# Dhuma.net
KiCad netlist of a schematic drawn in EAGLE
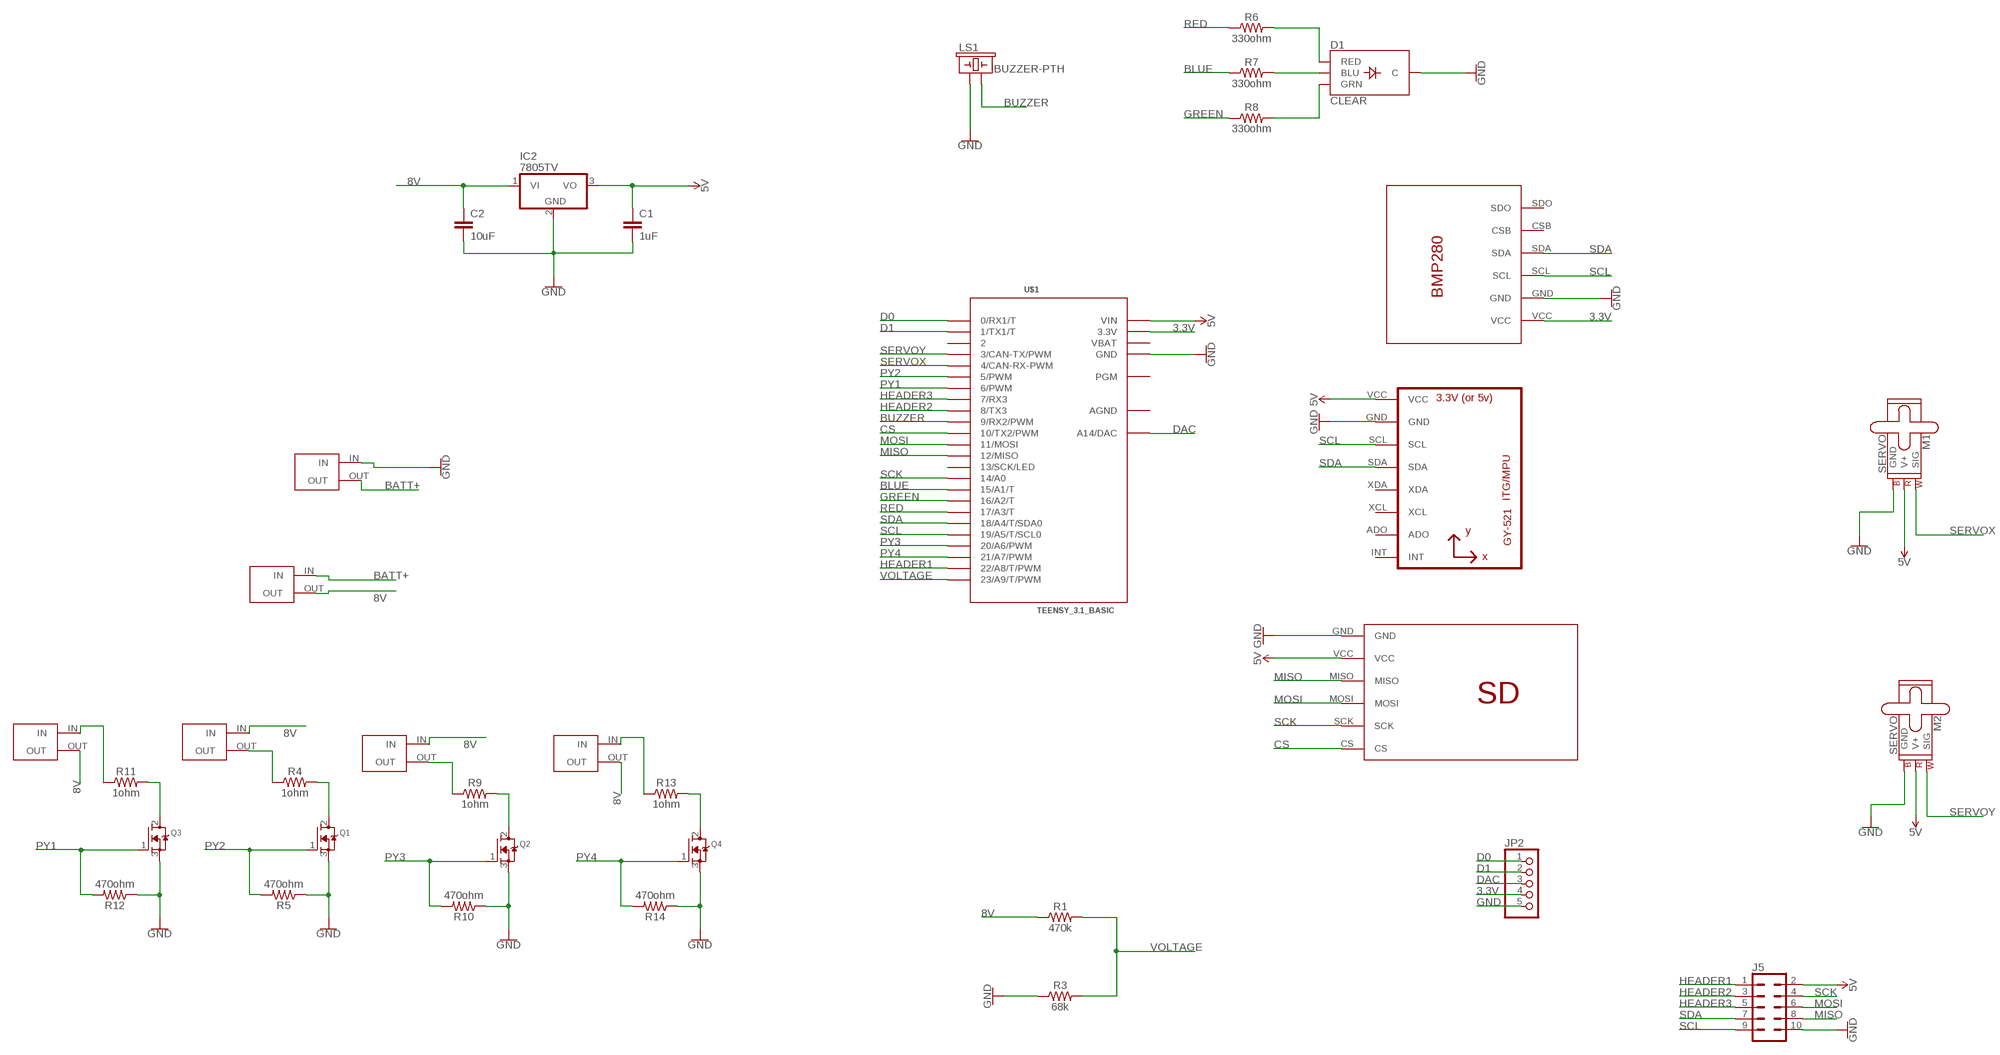
[diagram p0: schematic, sheet 1]

(export (version "E")
  (design (tool "Eeschema 10.0.6"))
  (components
    (comp (ref "C1")
      (value "1uF")
      (footprint "eagle-import:CAP-PTH-2.54")
      (libsource (lib "eagle-import") (part "22PF-PTH-2.54MM-200V-5%"))
    )
    (comp (ref "C2")
      (value "10uF")
      (footprint "eagle-import:CAP-PTH-2.54")
      (libsource (lib "eagle-import") (part "22PF-PTH-2.54MM-200V-5%"))
    )
    (comp (ref "D1")
      (value "CLEAR")
      (footprint "eagle-import:LED-RGB-THRU")
      (libsource (lib "eagle-import") (part "LED-RGB-CCCLEAR"))
    )
    (comp (ref "IC2")
      (value "7805TV")
      (footprint "eagle-import:TO220V")
      (libsource (lib "eagle-import") (part "78TV05"))
    )
    (comp (ref "J5")
      (value "CONN_05X2NO_SILK")
      (footprint "eagle-import:2X5_NOSILK")
      (libsource (lib "eagle-import") (part "CONN_05X2NO_SILK"))
    )
    (comp (ref "JP2")
      (value "PINHD-1X5")
      (footprint "eagle-import:1X05")
      (libsource (lib "eagle-import") (part "PINHD-1X5"))
    )
    (comp (ref "LS1")
      (value "BUZZER-PTH")
      (footprint "eagle-import:BUZZER-12MM")
      (libsource (lib "eagle-import") (part "BUZZER-PTH"))
    )
    (comp (ref "M1")
      (value "SERVO")
      (footprint "eagle-import:1X03")
      (libsource (lib "eagle-import") (part "SERVO"))
    )
    (comp (ref "M2")
      (value "SERVO")
      (footprint "eagle-import:1X03")
      (libsource (lib "eagle-import") (part "SERVO"))
    )
    (comp (ref "Q1")
      (value "MOSFET-NGDS_TO220V")
      (footprint "eagle-import:TO220V")
      (libsource (lib "eagle-import") (part "MOSFET-NGDS_TO220V"))
    )
    (comp (ref "Q2")
      (value "MOSFET-NGDS_TO220V")
      (footprint "eagle-import:TO220V")
      (libsource (lib "eagle-import") (part "MOSFET-NGDS_TO220V"))
    )
    (comp (ref "Q3")
      (value "MOSFET-NGDS_TO220V")
      (footprint "eagle-import:TO220V")
      (libsource (lib "eagle-import") (part "MOSFET-NGDS_TO220V"))
    )
    (comp (ref "Q4")
      (value "MOSFET-NGDS_TO220V")
      (footprint "eagle-import:TO220V")
      (libsource (lib "eagle-import") (part "MOSFET-NGDS_TO220V"))
    )
    (comp (ref "R1")
      (value "470k")
      (footprint "eagle-import:AXIAL-0.3")
      (libsource (lib "eagle-import") (part "10OHM-HORIZ-1/4W-1%"))
    )
    (comp (ref "R3")
      (value "68k")
      (footprint "eagle-import:AXIAL-0.3")
      (libsource (lib "eagle-import") (part "10OHM-HORIZ-1/4W-1%"))
    )
    (comp (ref "R4")
      (value "1ohm")
      (footprint "eagle-import:AXIAL-0.3")
      (libsource (lib "eagle-import") (part "10OHM-HORIZ-1/4W-1%"))
    )
    (comp (ref "R5")
      (value "470ohm")
      (footprint "eagle-import:AXIAL-0.3")
      (libsource (lib "eagle-import") (part "10OHM-HORIZ-1/4W-1%"))
    )
    (comp (ref "R6")
      (value "330ohm")
      (footprint "eagle-import:AXIAL-0.3")
      (libsource (lib "eagle-import") (part "10OHM-HORIZ-1/4W-1%"))
    )
    (comp (ref "R7")
      (value "330ohm")
      (footprint "eagle-import:AXIAL-0.3")
      (libsource (lib "eagle-import") (part "10OHM-HORIZ-1/4W-1%"))
    )
    (comp (ref "R8")
      (value "330ohm")
      (footprint "eagle-import:AXIAL-0.3")
      (libsource (lib "eagle-import") (part "10OHM-HORIZ-1/4W-1%"))
    )
    (comp (ref "R9")
      (value "1ohm")
      (footprint "eagle-import:AXIAL-0.3")
      (libsource (lib "eagle-import") (part "10OHM-HORIZ-1/4W-1%"))
    )
    (comp (ref "R10")
      (value "470ohm")
      (footprint "eagle-import:AXIAL-0.3")
      (libsource (lib "eagle-import") (part "10OHM-HORIZ-1/4W-1%"))
    )
    (comp (ref "R11")
      (value "1ohm")
      (footprint "eagle-import:AXIAL-0.3")
      (libsource (lib "eagle-import") (part "10OHM-HORIZ-1/4W-1%"))
    )
    (comp (ref "R12")
      (value "470ohm")
      (footprint "eagle-import:AXIAL-0.3")
      (libsource (lib "eagle-import") (part "10OHM-HORIZ-1/4W-1%"))
    )
    (comp (ref "R13")
      (value "1ohm")
      (footprint "eagle-import:AXIAL-0.3")
      (libsource (lib "eagle-import") (part "10OHM-HORIZ-1/4W-1%"))
    )
    (comp (ref "R14")
      (value "470ohm")
      (footprint "eagle-import:AXIAL-0.3")
      (libsource (lib "eagle-import") (part "10OHM-HORIZ-1/4W-1%"))
    )
    (comp (ref "U$1")
      (value "TEENSY_3.1_BASIC")
      (footprint "eagle-import:TEENSY_3.1_BASIC")
      (libsource (lib "eagle-import") (part "TEENSY_3.1_BASIC"))
    )
    (comp (ref "U$2")
      (value "BMP280")
      (footprint "eagle-import:BMP280")
      (libsource (lib "eagle-import") (part "BMP280"))
    )
    (comp (ref "U$3")
      (value "SDCARD")
      (footprint "eagle-import:SDCARD")
      (libsource (lib "eagle-import") (part "SDCARD"))
    )
    (comp (ref "U$4")
      (value "TERMINALBLOCKUP")
      (footprint "eagle-import:TERMINALBLOCKUP")
      (libsource (lib "eagle-import") (part "TERMINALBLOCKUP"))
    )
    (comp (ref "U$5")
      (value "TERMINALBLOCKUP")
      (footprint "eagle-import:TERMINALBLOCKUP")
      (libsource (lib "eagle-import") (part "TERMINALBLOCKUP"))
    )
    (comp (ref "U$6")
      (value "TERMINALBLOCKUP")
      (footprint "eagle-import:TERMINALBLOCKUP")
      (libsource (lib "eagle-import") (part "TERMINALBLOCKUP"))
    )
    (comp (ref "U$7")
      (value "TERMINALBLOCKUP")
      (footprint "eagle-import:TERMINALBLOCKUP")
      (libsource (lib "eagle-import") (part "TERMINALBLOCKUP"))
    )
    (comp (ref "U$8")
      (value "TERMINALBLOCKUP")
      (footprint "eagle-import:TERMINALBLOCKUP")
      (libsource (lib "eagle-import") (part "TERMINALBLOCKUP"))
    )
    (comp (ref "U$9")
      (value "TERMINALBLOCKUP")
      (footprint "eagle-import:TERMINALBLOCKUP")
      (libsource (lib "eagle-import") (part "TERMINALBLOCKUP"))
    )
    (comp (ref "U1")
      (value "GY-521MPU6050")
      (footprint "eagle-import:GY-521")
      (libsource (lib "eagle-import") (part "GY-521MPU6050"))
    )
  )
  (nets
    (net (code "1") (name "/3.3V") (class "Default")
      (node (ref "JP2") (pin "4") (pinfunction "4_4") (pintype "passive"))
      (node (ref "U$1") (pin "3.3V") (pinfunction "3.3V_3.3V") (pintype "power_in"))
      (node (ref "U$1") (pin "3.3V1") (pinfunction "3.3V_3.3V1") (pintype "power_in"))
      (node (ref "U$2") (pin "VCC") (pinfunction "VCC_VCC") (pintype "bidirectional"))
    )
    (net (code "2") (name "/8V") (class "Default")
      (node (ref "C2") (pin "1") (pinfunction "1_1") (pintype "passive"))
      (node (ref "IC2") (pin "1") (pinfunction "VI_1") (pintype "input"))
      (node (ref "R1") (pin "P$1") (pinfunction "1_P$1") (pintype "passive"))
      (node (ref "U$4") (pin "IN") (pinfunction "IN_IN") (pintype "bidirectional"))
      (node (ref "U$5") (pin "OUT") (pinfunction "OUT_OUT") (pintype "bidirectional"))
      (node (ref "U$6") (pin "IN") (pinfunction "IN_IN") (pintype "bidirectional"))
      (node (ref "U$7") (pin "OUT") (pinfunction "OUT_OUT") (pintype "bidirectional"))
      (node (ref "U$9") (pin "OUT") (pinfunction "OUT_OUT") (pintype "bidirectional"))
    )
    (net (code "3") (name "/AGND") (class "Default")
      (node (ref "U$1") (pin "AGND") (pinfunction "AGND_AGND") (pintype "power_in"))
    )
    (net (code "4") (name "/BATT+") (class "Default")
      (node (ref "U$8") (pin "OUT") (pinfunction "OUT_OUT") (pintype "bidirectional"))
      (node (ref "U$9") (pin "IN") (pinfunction "IN_IN") (pintype "bidirectional"))
    )
    (net (code "5") (name "/BLUE") (class "Default")
      (node (ref "R7") (pin "P$1") (pinfunction "1_P$1") (pintype "passive"))
      (node (ref "U$1") (pin "15/A1") (pinfunction "15/A1/T_15/A1") (pintype "bidirectional"))
    )
    (net (code "6") (name "/BUZZER") (class "Default")
      (node (ref "LS1") (pin "-") (pinfunction "2_-") (pintype "passive"))
      (node (ref "U$1") (pin "9") (pinfunction "9/RX2/PWM_9") (pintype "bidirectional"))
    )
    (net (code "7") (name "/CS") (class "Default")
      (node (ref "U$1") (pin "10") (pinfunction "10/TX2/PWM_10") (pintype "bidirectional"))
      (node (ref "U$3") (pin "CS") (pinfunction "CS_CS") (pintype "bidirectional"))
    )
    (net (code "8") (name "/D0") (class "Default")
      (node (ref "JP2") (pin "1") (pinfunction "1_1") (pintype "passive"))
      (node (ref "U$1") (pin "0") (pinfunction "0/RX1/T_0") (pintype "bidirectional"))
    )
    (net (code "9") (name "/D1") (class "Default")
      (node (ref "JP2") (pin "2") (pinfunction "2_2") (pintype "passive"))
      (node (ref "U$1") (pin "1") (pinfunction "1/TX1/T_1") (pintype "bidirectional"))
    )
    (net (code "10") (name "/DAC") (class "Default")
      (node (ref "JP2") (pin "3") (pinfunction "3_3") (pintype "passive"))
      (node (ref "U$1") (pin "A14") (pinfunction "A14/DAC_A14") (pintype "bidirectional"))
    )
    (net (code "11") (name "/GREEN") (class "Default")
      (node (ref "R8") (pin "P$1") (pinfunction "1_P$1") (pintype "passive"))
      (node (ref "U$1") (pin "16/A2") (pinfunction "16/A2/T_16/A2") (pintype "bidirectional"))
    )
    (net (code "12") (name "/HEADER1") (class "Default")
      (node (ref "J5") (pin "1") (pinfunction "1_1") (pintype "passive"))
      (node (ref "U$1") (pin "22/A8") (pinfunction "22/A8/T/PWM_22/A8") (pintype "bidirectional"))
    )
    (net (code "13") (name "/HEADER2") (class "Default")
      (node (ref "J5") (pin "3") (pinfunction "3_3") (pintype "passive"))
      (node (ref "U$1") (pin "8") (pinfunction "8/TX3_8") (pintype "bidirectional"))
    )
    (net (code "14") (name "/HEADER3") (class "Default")
      (node (ref "J5") (pin "5") (pinfunction "5_5") (pintype "passive"))
      (node (ref "U$1") (pin "7") (pinfunction "7/RX3_7") (pintype "bidirectional"))
    )
    (net (code "15") (name "/MISO") (class "Default")
      (node (ref "J5") (pin "8") (pinfunction "8_8") (pintype "passive"))
      (node (ref "U$1") (pin "12") (pinfunction "12/MISO_12") (pintype "bidirectional"))
      (node (ref "U$3") (pin "MISO") (pinfunction "MISO_MISO") (pintype "bidirectional"))
    )
    (net (code "16") (name "/MOSI") (class "Default")
      (node (ref "J5") (pin "6") (pinfunction "6_6") (pintype "passive"))
      (node (ref "U$1") (pin "11") (pinfunction "11/MOSI_11") (pintype "bidirectional"))
      (node (ref "U$3") (pin "MOSI") (pinfunction "MOSI_MOSI") (pintype "bidirectional"))
    )
    (net (code "17") (name "/PY1") (class "Default")
      (node (ref "Q3") (pin "1") (pinfunction "G_1") (pintype "bidirectional"))
      (node (ref "R12") (pin "P$2") (pinfunction "2_P$2") (pintype "passive"))
      (node (ref "U$1") (pin "6") (pinfunction "6/PWM_6") (pintype "bidirectional"))
    )
    (net (code "18") (name "/PY2") (class "Default")
      (node (ref "Q1") (pin "1") (pinfunction "G_1") (pintype "bidirectional"))
      (node (ref "R5") (pin "P$2") (pinfunction "2_P$2") (pintype "passive"))
      (node (ref "U$1") (pin "5") (pinfunction "5/PWM_5") (pintype "bidirectional"))
    )
    (net (code "19") (name "/PY3") (class "Default")
      (node (ref "Q2") (pin "1") (pinfunction "G_1") (pintype "bidirectional"))
      (node (ref "R10") (pin "P$2") (pinfunction "2_P$2") (pintype "passive"))
      (node (ref "U$1") (pin "20/A6") (pinfunction "20/A6/PWM_20/A6") (pintype "bidirectional"))
    )
    (net (code "20") (name "/PY4") (class "Default")
      (node (ref "Q4") (pin "1") (pinfunction "G_1") (pintype "bidirectional"))
      (node (ref "R14") (pin "P$2") (pinfunction "2_P$2") (pintype "passive"))
      (node (ref "U$1") (pin "21/A7") (pinfunction "21/A7/PWM_21/A7") (pintype "bidirectional"))
    )
    (net (code "21") (name "/RED") (class "Default")
      (node (ref "R6") (pin "P$1") (pinfunction "1_P$1") (pintype "passive"))
      (node (ref "U$1") (pin "17/A3") (pinfunction "17/A3/T_17/A3") (pintype "bidirectional"))
    )
    (net (code "22") (name "/SCK") (class "Default")
      (node (ref "J5") (pin "4") (pinfunction "4_4") (pintype "passive"))
      (node (ref "U$1") (pin "14/A0") (pinfunction "14/A0_14/A0") (pintype "bidirectional"))
      (node (ref "U$3") (pin "SCK") (pinfunction "SCK_SCK") (pintype "bidirectional"))
    )
    (net (code "23") (name "/SCL") (class "Default")
      (node (ref "J5") (pin "9") (pinfunction "9_9") (pintype "passive"))
      (node (ref "U$1") (pin "19/A5") (pinfunction "19/A5/T/SCL0_19/A5") (pintype "bidirectional"))
      (node (ref "U$2") (pin "SCL") (pinfunction "SCL_SCL") (pintype "bidirectional"))
      (node (ref "U1") (pin "SCL") (pinfunction "SCL_SCL") (pintype "bidirectional"))
    )
    (net (code "24") (name "/SDA") (class "Default")
      (node (ref "J5") (pin "7") (pinfunction "7_7") (pintype "passive"))
      (node (ref "U$1") (pin "18/A4") (pinfunction "18/A4/T/SDA0_18/A4") (pintype "bidirectional"))
      (node (ref "U$2") (pin "SDA") (pinfunction "SDA_SDA") (pintype "bidirectional"))
      (node (ref "U1") (pin "SDA") (pinfunction "SDA_SDA") (pintype "bidirectional"))
    )
    (net (code "25") (name "/SERVOX") (class "Default")
      (node (ref "M1") (pin "1") (pinfunction "SIG_1") (pintype "bidirectional"))
      (node (ref "U$1") (pin "4") (pinfunction "4/CAN-RX-PWM_4") (pintype "bidirectional"))
    )
    (net (code "26") (name "/SERVOY") (class "Default")
      (node (ref "M2") (pin "1") (pinfunction "SIG_1") (pintype "bidirectional"))
      (node (ref "U$1") (pin "3") (pinfunction "3/CAN-TX/PWM_3") (pintype "bidirectional"))
    )
    (net (code "27") (name "/VBAT") (class "Default")
      (node (ref "U$1") (pin "VBAT") (pinfunction "VBAT_VBAT") (pintype "power_in"))
    )
    (net (code "28") (name "/VOLTAGE") (class "Default")
      (node (ref "R1") (pin "P$2") (pinfunction "2_P$2") (pintype "passive"))
      (node (ref "R3") (pin "P$2") (pinfunction "2_P$2") (pintype "passive"))
      (node (ref "U$1") (pin "23/A9") (pinfunction "23/A9/T/PWM_23/A9") (pintype "bidirectional"))
    )
    (net (code "29") (name "5V") (class "Default")
      (node (ref "C1") (pin "1") (pinfunction "1_1") (pintype "passive"))
      (node (ref "IC2") (pin "3") (pinfunction "VO_3") (pintype "passive"))
      (node (ref "J5") (pin "2") (pinfunction "2_2") (pintype "passive"))
      (node (ref "M1") (pin "2") (pinfunction "V+_2") (pintype "bidirectional"))
      (node (ref "M2") (pin "2") (pinfunction "V+_2") (pintype "bidirectional"))
      (node (ref "U$1") (pin "VIN") (pinfunction "VIN_VIN") (pintype "power_in"))
      (node (ref "U$3") (pin "VCC") (pinfunction "VCC_VCC") (pintype "bidirectional"))
      (node (ref "U1") (pin "VCC") (pinfunction "VCC_VCC") (pintype "bidirectional"))
    )
    (net (code "30") (name "GND") (class "Default")
      (node (ref "C1") (pin "2") (pinfunction "2_2") (pintype "passive"))
      (node (ref "C2") (pin "2") (pinfunction "2_2") (pintype "passive"))
      (node (ref "D1") (pin "2") (pinfunction "C_2") (pintype "bidirectional"))
      (node (ref "IC2") (pin "2") (pinfunction "GND_2") (pintype "passive"))
      (node (ref "J5") (pin "10") (pinfunction "10_10") (pintype "passive"))
      (node (ref "JP2") (pin "5") (pinfunction "5_5") (pintype "passive"))
      (node (ref "LS1") (pin "+") (pinfunction "1_+") (pintype "passive"))
      (node (ref "M1") (pin "3") (pinfunction "GND_3") (pintype "bidirectional"))
      (node (ref "M2") (pin "3") (pinfunction "GND_3") (pintype "bidirectional"))
      (node (ref "Q1") (pin "3") (pinfunction "S_3") (pintype "bidirectional"))
      (node (ref "Q2") (pin "3") (pinfunction "S_3") (pintype "bidirectional"))
      (node (ref "Q3") (pin "3") (pinfunction "S_3") (pintype "bidirectional"))
      (node (ref "Q4") (pin "3") (pinfunction "S_3") (pintype "bidirectional"))
      (node (ref "R10") (pin "P$1") (pinfunction "1_P$1") (pintype "passive"))
      (node (ref "R12") (pin "P$1") (pinfunction "1_P$1") (pintype "passive"))
      (node (ref "R14") (pin "P$1") (pinfunction "1_P$1") (pintype "passive"))
      (node (ref "R3") (pin "P$1") (pinfunction "1_P$1") (pintype "passive"))
      (node (ref "R5") (pin "P$1") (pinfunction "1_P$1") (pintype "passive"))
      (node (ref "U$1") (pin "GND") (pinfunction "GND_GND") (pintype "power_in"))
      (node (ref "U$1") (pin "GND1") (pinfunction "GND_GND1") (pintype "power_in"))
      (node (ref "U$2") (pin "GND") (pinfunction "GND_GND") (pintype "bidirectional"))
      (node (ref "U$3") (pin "GND") (pinfunction "GND_GND") (pintype "bidirectional"))
      (node (ref "U$8") (pin "IN") (pinfunction "IN_IN") (pintype "bidirectional"))
      (node (ref "U1") (pin "GND") (pinfunction "GND_GND") (pintype "bidirectional"))
    )
    (net (code "31") (name "Net-(D1-BLU)") (class "Default")
      (node (ref "D1") (pin "4") (pinfunction "BLU_4") (pintype "bidirectional"))
      (node (ref "R7") (pin "P$2") (pinfunction "2_P$2") (pintype "passive"))
    )
    (net (code "32") (name "Net-(D1-GRN)") (class "Default")
      (node (ref "D1") (pin "3") (pinfunction "GRN_3") (pintype "bidirectional"))
      (node (ref "R8") (pin "P$2") (pinfunction "2_P$2") (pintype "passive"))
    )
    (net (code "33") (name "Net-(D1-RED)") (class "Default")
      (node (ref "D1") (pin "1") (pinfunction "RED_1") (pintype "bidirectional"))
      (node (ref "R6") (pin "P$2") (pinfunction "2_P$2") (pintype "passive"))
    )
    (net (code "34") (name "Net-(Q1-D)") (class "Default")
      (node (ref "Q1") (pin "2") (pinfunction "D_2") (pintype "bidirectional"))
      (node (ref "R4") (pin "P$2") (pinfunction "2_P$2") (pintype "passive"))
    )
    (net (code "35") (name "Net-(Q2-D)") (class "Default")
      (node (ref "Q2") (pin "2") (pinfunction "D_2") (pintype "bidirectional"))
      (node (ref "R9") (pin "P$2") (pinfunction "2_P$2") (pintype "passive"))
    )
    (net (code "36") (name "Net-(Q3-D)") (class "Default")
      (node (ref "Q3") (pin "2") (pinfunction "D_2") (pintype "bidirectional"))
      (node (ref "R11") (pin "P$2") (pinfunction "2_P$2") (pintype "passive"))
    )
    (net (code "37") (name "Net-(Q4-D)") (class "Default")
      (node (ref "Q4") (pin "2") (pinfunction "D_2") (pintype "bidirectional"))
      (node (ref "R13") (pin "P$2") (pinfunction "2_P$2") (pintype "passive"))
    )
    (net (code "38") (name "Net-(R4-1)") (class "Default")
      (node (ref "R4") (pin "P$1") (pinfunction "1_P$1") (pintype "passive"))
      (node (ref "U$4") (pin "OUT") (pinfunction "OUT_OUT") (pintype "bidirectional"))
    )
    (net (code "39") (name "Net-(R9-1)") (class "Default")
      (node (ref "R9") (pin "P$1") (pinfunction "1_P$1") (pintype "passive"))
      (node (ref "U$6") (pin "OUT") (pinfunction "OUT_OUT") (pintype "bidirectional"))
    )
    (net (code "40") (name "Net-(R11-1)") (class "Default")
      (node (ref "R11") (pin "P$1") (pinfunction "1_P$1") (pintype "passive"))
      (node (ref "U$5") (pin "IN") (pinfunction "IN_IN") (pintype "bidirectional"))
    )
    (net (code "41") (name "Net-(R13-1)") (class "Default")
      (node (ref "R13") (pin "P$1") (pinfunction "1_P$1") (pintype "passive"))
      (node (ref "U$7") (pin "IN") (pinfunction "IN_IN") (pintype "bidirectional"))
    )
    (net (code "42") (name "unconnected-(U$1-13{slash}SCK{slash}LED-Pad13)") (class "Default")
      (node (ref "U$1") (pin "13") (pinfunction "13/SCK/LED_13") (pintype "bidirectional"))
    )
    (net (code "43") (name "unconnected-(U$1-Pad2)") (class "Default")
      (node (ref "U$1") (pin "2") (pinfunction "2_2") (pintype "bidirectional"))
    )
    (net (code "44") (name "unconnected-(U$1-PadPGM)") (class "Default")
      (node (ref "U$1") (pin "PGM") (pinfunction "PGM_PGM") (pintype "bidirectional"))
    )
    (net (code "45") (name "unconnected-(U$2-PadCSB)") (class "Default")
      (node (ref "U$2") (pin "CSB") (pinfunction "CSB_CSB") (pintype "bidirectional"))
    )
    (net (code "46") (name "unconnected-(U$2-PadSDO)") (class "Default")
      (node (ref "U$2") (pin "SDO") (pinfunction "SDO_SDO") (pintype "bidirectional"))
    )
    (net (code "47") (name "unconnected-(U1-PadADO)") (class "Default")
      (node (ref "U1") (pin "ADO") (pinfunction "ADO_ADO") (pintype "bidirectional"))
    )
    (net (code "48") (name "unconnected-(U1-PadINT)") (class "Default")
      (node (ref "U1") (pin "INT") (pinfunction "INT_INT") (pintype "bidirectional"))
    )
    (net (code "49") (name "unconnected-(U1-PadXCL)") (class "Default")
      (node (ref "U1") (pin "XCL") (pinfunction "XCL_XCL") (pintype "bidirectional"))
    )
    (net (code "50") (name "unconnected-(U1-PadXDA)") (class "Default")
      (node (ref "U1") (pin "XDA") (pinfunction "XDA_XDA") (pintype "bidirectional"))
    )
  )
)
